# kitpic.net
KiCad netlist of a schematic drawn in Altium Designer
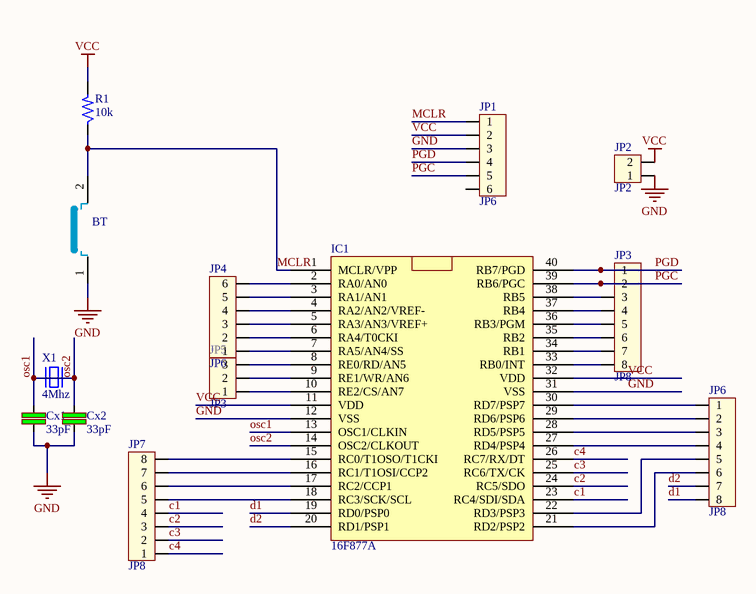
[diagram p0: kitpic.SchDoc]

(export (version "E")
  (design (tool "Eeschema 10.0.6"))
  (components
    (comp (ref "BT1") (value "BT") (footprint "SW4") (libsource (lib "My library altium") (part "BUTTON")))
    (comp (ref "Cx1")
      (value "33pF")
      (footprint "CN1")
      (description "Cremic For Xtal 1pF => 100pF")
      (libsource (lib "Library AL") (part "CN0"))
    )
    (comp (ref "Cx2")
      (value "33pF")
      (footprint "CN1")
      (description "Cremic For Xtal 1pF => 100pF")
      (libsource (lib "Library AL") (part "CN0"))
    )
    (comp (ref "IC1")
      (value "16F877A")
      (footprint "DIP40/W0.6")
      (libsource (lib "My library altium") (part "PIC 16F877A"))
    )
    (comp (ref "JP1")
      (value "JP6")
      (footprint "CON6")
      (description "Connector 6")
      (libsource (lib "Library AL") (part "Con6"))
    )
    (comp (ref "JP2")
      (value "JP2")
      (footprint "CON2")
      (description "Connector 2")
      (libsource (lib "Library AL") (part "Con2"))
    )
    (comp (ref "JP3")
      (value "JP8")
      (footprint "CON8")
      (description "Connector 8")
      (libsource (lib "") (part "Con8_1"))
    )
    (comp (ref "JP4")
      (value "JP6")
      (footprint "CON6")
      (description "Connector 6")
      (libsource (lib "") (part "Con6_1"))
    )
    (comp (ref "JP5")
      (value "JP3")
      (footprint "CON3")
      (description "Connector 3")
      (libsource (lib "Library AL") (part "Con3"))
    )
    (comp (ref "JP6")
      (value "JP8")
      (footprint "CON8")
      (description "Connector 8")
      (libsource (lib "") (part "Con8_1"))
    )
    (comp (ref "JP7")
      (value "JP8")
      (footprint "CON8")
      (description "Connector 8")
      (libsource (lib "Library AL") (part "Con8"))
    )
    (comp (ref "R1")
      (value "10k")
      (footprint "R1/4W")
      (description "Res")
      (libsource (lib "My library altium") (part "Res"))
    )
    (comp (ref "X1")
      (value "4Mhz")
      (footprint "XT2")
      (description "Crystal For all Crystal 2pin.")
      (libsource (lib "Library AL") (part "XT2"))
    )
  )
  (nets
    (net (code "1") (name "/MCLR") (class "Default")
      (node (ref "BT1") (pin "2") (pinfunction "2_2") (pintype "passive"))
      (node (ref "IC1") (pin "1") (pinfunction "MCLR/VPP_1") (pintype "passive"))
      (node (ref "JP1") (pin "1") (pinfunction "1_1") (pintype "passive"))
      (node (ref "R1") (pin "1") (pinfunction "1_1") (pintype "passive"))
    )
    (net (code "2") (name "/PGC") (class "Default")
      (node (ref "IC1") (pin "39") (pinfunction "RB6/PGC_39") (pintype "passive"))
      (node (ref "JP1") (pin "5") (pinfunction "5_5") (pintype "passive"))
      (node (ref "JP3") (pin "2") (pinfunction "2_2") (pintype "passive"))
    )
    (net (code "3") (name "/PGD") (class "Default")
      (node (ref "IC1") (pin "40") (pinfunction "RB7/PGD_40") (pintype "passive"))
      (node (ref "JP1") (pin "4") (pinfunction "4_4") (pintype "passive"))
      (node (ref "JP3") (pin "1") (pinfunction "1_1") (pintype "passive"))
    )
    (net (code "4") (name "/c1") (class "Default")
      (node (ref "IC1") (pin "23") (pinfunction "RC4/SDI/SDA_23") (pintype "passive"))
      (node (ref "JP7") (pin "4") (pinfunction "4_4") (pintype "passive"))
    )
    (net (code "5") (name "/c2") (class "Default")
      (node (ref "IC1") (pin "24") (pinfunction "RC5/SDO_24") (pintype "passive"))
      (node (ref "JP7") (pin "3") (pinfunction "3_3") (pintype "passive"))
    )
    (net (code "6") (name "/c3") (class "Default")
      (node (ref "IC1") (pin "25") (pinfunction "RC6/TX/CK_25") (pintype "passive"))
      (node (ref "JP7") (pin "2") (pinfunction "2_2") (pintype "passive"))
    )
    (net (code "7") (name "/c4") (class "Default")
      (node (ref "IC1") (pin "26") (pinfunction "RC7/RX/DT_26") (pintype "passive"))
      (node (ref "JP7") (pin "1") (pinfunction "1_1") (pintype "passive"))
    )
    (net (code "8") (name "/d1") (class "Default")
      (node (ref "IC1") (pin "19") (pinfunction "RD0/PSP0_19") (pintype "passive"))
      (node (ref "JP6") (pin "8") (pinfunction "8_8") (pintype "passive"))
    )
    (net (code "9") (name "/d2") (class "Default")
      (node (ref "IC1") (pin "20") (pinfunction "RD1/PSP1_20") (pintype "passive"))
      (node (ref "JP6") (pin "7") (pinfunction "7_7") (pintype "passive"))
    )
    (net (code "10") (name "/osc1") (class "Default")
      (node (ref "Cx1") (pin "2") (pinfunction "2_2") (pintype "passive"))
      (node (ref "Cx2") (pin "2") (pinfunction "2_2") (pintype "passive"))
      (node (ref "IC1") (pin "13") (pinfunction "OSC1/CLKIN_13") (pintype "passive"))
      (node (ref "IC1") (pin "14") (pinfunction "OSC2/CLKOUT_14") (pintype "passive"))
      (node (ref "X1") (pin "1") (pinfunction "1_1") (pintype "passive"))
      (node (ref "X1") (pin "2") (pinfunction "2_2") (pintype "passive"))
    )
    (net (code "11") (name "GND") (class "Default")
      (node (ref "BT1") (pin "1") (pinfunction "1_1") (pintype "passive"))
      (node (ref "Cx1") (pin "1") (pinfunction "1_1") (pintype "passive"))
      (node (ref "Cx2") (pin "1") (pinfunction "1_1") (pintype "passive"))
      (node (ref "IC1") (pin "12") (pinfunction "VSS_12") (pintype "passive"))
      (node (ref "IC1") (pin "31") (pinfunction "VSS_31") (pintype "passive"))
      (node (ref "JP1") (pin "3") (pinfunction "3_3") (pintype "passive"))
      (node (ref "JP2") (pin "1") (pinfunction "1_1") (pintype "passive"))
    )
    (net (code "12") (name "Net-(IC1-RA0{slash}AN0)") (class "Default")
      (node (ref "IC1") (pin "2") (pinfunction "RA0/AN0_2") (pintype "passive"))
      (node (ref "JP4") (pin "6") (pinfunction "6_6") (pintype "passive"))
    )
    (net (code "13") (name "Net-(IC1-RA1{slash}AN1)") (class "Default")
      (node (ref "IC1") (pin "3") (pinfunction "RA1/AN1_3") (pintype "passive"))
      (node (ref "JP4") (pin "5") (pinfunction "5_5") (pintype "passive"))
    )
    (net (code "14") (name "Net-(IC1-RA2{slash}AN2{slash}VREF-)") (class "Default")
      (node (ref "IC1") (pin "4") (pinfunction "RA2/AN2/VREF-_4") (pintype "passive"))
      (node (ref "JP4") (pin "4") (pinfunction "4_4") (pintype "passive"))
    )
    (net (code "15") (name "Net-(IC1-RA3{slash}AN3{slash}VREF+)") (class "Default")
      (node (ref "IC1") (pin "5") (pinfunction "RA3/AN3/VREF+_5") (pintype "passive"))
      (node (ref "JP4") (pin "3") (pinfunction "3_3") (pintype "passive"))
    )
    (net (code "16") (name "Net-(IC1-RA4{slash}T0CKI)") (class "Default")
      (node (ref "IC1") (pin "6") (pinfunction "RA4/T0CKI_6") (pintype "passive"))
      (node (ref "JP4") (pin "2") (pinfunction "2_2") (pintype "passive"))
    )
    (net (code "17") (name "Net-(IC1-RA5{slash}AN4{slash}SS)") (class "Default")
      (node (ref "IC1") (pin "7") (pinfunction "RA5/AN4/SS_7") (pintype "passive"))
      (node (ref "JP4") (pin "1") (pinfunction "1_1") (pintype "passive"))
    )
    (net (code "18") (name "Net-(IC1-RB0{slash}INT)") (class "Default")
      (node (ref "IC1") (pin "33") (pinfunction "RB0/INT_33") (pintype "passive"))
      (node (ref "JP3") (pin "8") (pinfunction "8_8") (pintype "passive"))
    )
    (net (code "19") (name "Net-(IC1-RB1)") (class "Default")
      (node (ref "IC1") (pin "34") (pinfunction "RB1_34") (pintype "passive"))
      (node (ref "JP3") (pin "7") (pinfunction "7_7") (pintype "passive"))
    )
    (net (code "20") (name "Net-(IC1-RB2)") (class "Default")
      (node (ref "IC1") (pin "35") (pinfunction "RB2_35") (pintype "passive"))
      (node (ref "JP3") (pin "6") (pinfunction "6_6") (pintype "passive"))
    )
    (net (code "21") (name "Net-(IC1-RB3{slash}PGM)") (class "Default")
      (node (ref "IC1") (pin "36") (pinfunction "RB3/PGM_36") (pintype "passive"))
      (node (ref "JP3") (pin "5") (pinfunction "5_5") (pintype "passive"))
    )
    (net (code "22") (name "Net-(IC1-RB4)") (class "Default")
      (node (ref "IC1") (pin "37") (pinfunction "RB4_37") (pintype "passive"))
      (node (ref "JP3") (pin "4") (pinfunction "4_4") (pintype "passive"))
    )
    (net (code "23") (name "Net-(IC1-RB5)") (class "Default")
      (node (ref "IC1") (pin "38") (pinfunction "RB5_38") (pintype "passive"))
      (node (ref "JP3") (pin "3") (pinfunction "3_3") (pintype "passive"))
    )
    (net (code "24") (name "Net-(IC1-RC0{slash}T1OSO{slash}T1CKI)") (class "Default")
      (node (ref "IC1") (pin "15") (pinfunction "RC0/T1OSO/T1CKI_15") (pintype "passive"))
      (node (ref "JP7") (pin "8") (pinfunction "8_8") (pintype "passive"))
    )
    (net (code "25") (name "Net-(IC1-RC1{slash}T1OSI{slash}CCP2)") (class "Default")
      (node (ref "IC1") (pin "16") (pinfunction "RC1/T1OSI/CCP2_16") (pintype "passive"))
      (node (ref "JP7") (pin "7") (pinfunction "7_7") (pintype "passive"))
    )
    (net (code "26") (name "Net-(IC1-RC2{slash}CCP1)") (class "Default")
      (node (ref "IC1") (pin "17") (pinfunction "RC2/CCP1_17") (pintype "passive"))
      (node (ref "JP7") (pin "6") (pinfunction "6_6") (pintype "passive"))
    )
    (net (code "27") (name "Net-(IC1-RC3{slash}SCK{slash}SCL)") (class "Default")
      (node (ref "IC1") (pin "18") (pinfunction "RC3/SCK/SCL_18") (pintype "passive"))
      (node (ref "JP7") (pin "5") (pinfunction "5_5") (pintype "passive"))
    )
    (net (code "28") (name "Net-(IC1-RD2{slash}PSP2)") (class "Default")
      (node (ref "IC1") (pin "21") (pinfunction "RD2/PSP2_21") (pintype "passive"))
      (node (ref "JP6") (pin "6") (pinfunction "6_6") (pintype "passive"))
    )
    (net (code "29") (name "Net-(IC1-RD3{slash}PSP3)") (class "Default")
      (node (ref "IC1") (pin "22") (pinfunction "RD3/PSP3_22") (pintype "passive"))
      (node (ref "JP6") (pin "5") (pinfunction "5_5") (pintype "passive"))
    )
    (net (code "30") (name "Net-(IC1-RD4{slash}PSP4)") (class "Default")
      (node (ref "IC1") (pin "27") (pinfunction "RD4/PSP4_27") (pintype "passive"))
      (node (ref "JP6") (pin "4") (pinfunction "4_4") (pintype "passive"))
    )
    (net (code "31") (name "Net-(IC1-RD5{slash}PSP5)") (class "Default")
      (node (ref "IC1") (pin "28") (pinfunction "RD5/PSP5_28") (pintype "passive"))
      (node (ref "JP6") (pin "3") (pinfunction "3_3") (pintype "passive"))
    )
    (net (code "32") (name "Net-(IC1-RD6{slash}PSP6)") (class "Default")
      (node (ref "IC1") (pin "29") (pinfunction "RD6/PSP6_29") (pintype "passive"))
      (node (ref "JP6") (pin "2") (pinfunction "2_2") (pintype "passive"))
    )
    (net (code "33") (name "Net-(IC1-RD7{slash}PSP7)") (class "Default")
      (node (ref "IC1") (pin "30") (pinfunction "RD7/PSP7_30") (pintype "passive"))
      (node (ref "JP6") (pin "1") (pinfunction "1_1") (pintype "passive"))
    )
    (net (code "34") (name "Net-(IC1-RE0{slash}RD{slash}AN5)") (class "Default")
      (node (ref "IC1") (pin "8") (pinfunction "RE0/RD/AN5_8") (pintype "passive"))
      (node (ref "JP5") (pin "3") (pinfunction "3_3") (pintype "passive"))
    )
    (net (code "35") (name "Net-(IC1-RE1{slash}WR{slash}AN6)") (class "Default")
      (node (ref "IC1") (pin "9") (pinfunction "RE1/WR/AN6_9") (pintype "passive"))
      (node (ref "JP5") (pin "2") (pinfunction "2_2") (pintype "passive"))
    )
    (net (code "36") (name "Net-(IC1-RE2{slash}CS{slash}AN7)") (class "Default")
      (node (ref "IC1") (pin "10") (pinfunction "RE2/CS/AN7_10") (pintype "passive"))
      (node (ref "JP5") (pin "1") (pinfunction "1_1") (pintype "passive"))
    )
    (net (code "37") (name "VCC") (class "Default")
      (node (ref "IC1") (pin "11") (pinfunction "VDD_11") (pintype "passive"))
      (node (ref "IC1") (pin "32") (pinfunction "VDD_32") (pintype "passive"))
      (node (ref "JP1") (pin "2") (pinfunction "2_2") (pintype "passive"))
      (node (ref "JP2") (pin "2") (pinfunction "2_2") (pintype "passive"))
      (node (ref "R1") (pin "2") (pinfunction "2_2") (pintype "passive"))
    )
    (net (code "38") (name "unconnected-(JP1-Pad6)") (class "Default")
      (node (ref "JP1") (pin "6") (pinfunction "6_6") (pintype "passive"))
    )
  )
)
